# megamon.net
KiCad netlist of a schematic drawn in EAGLE
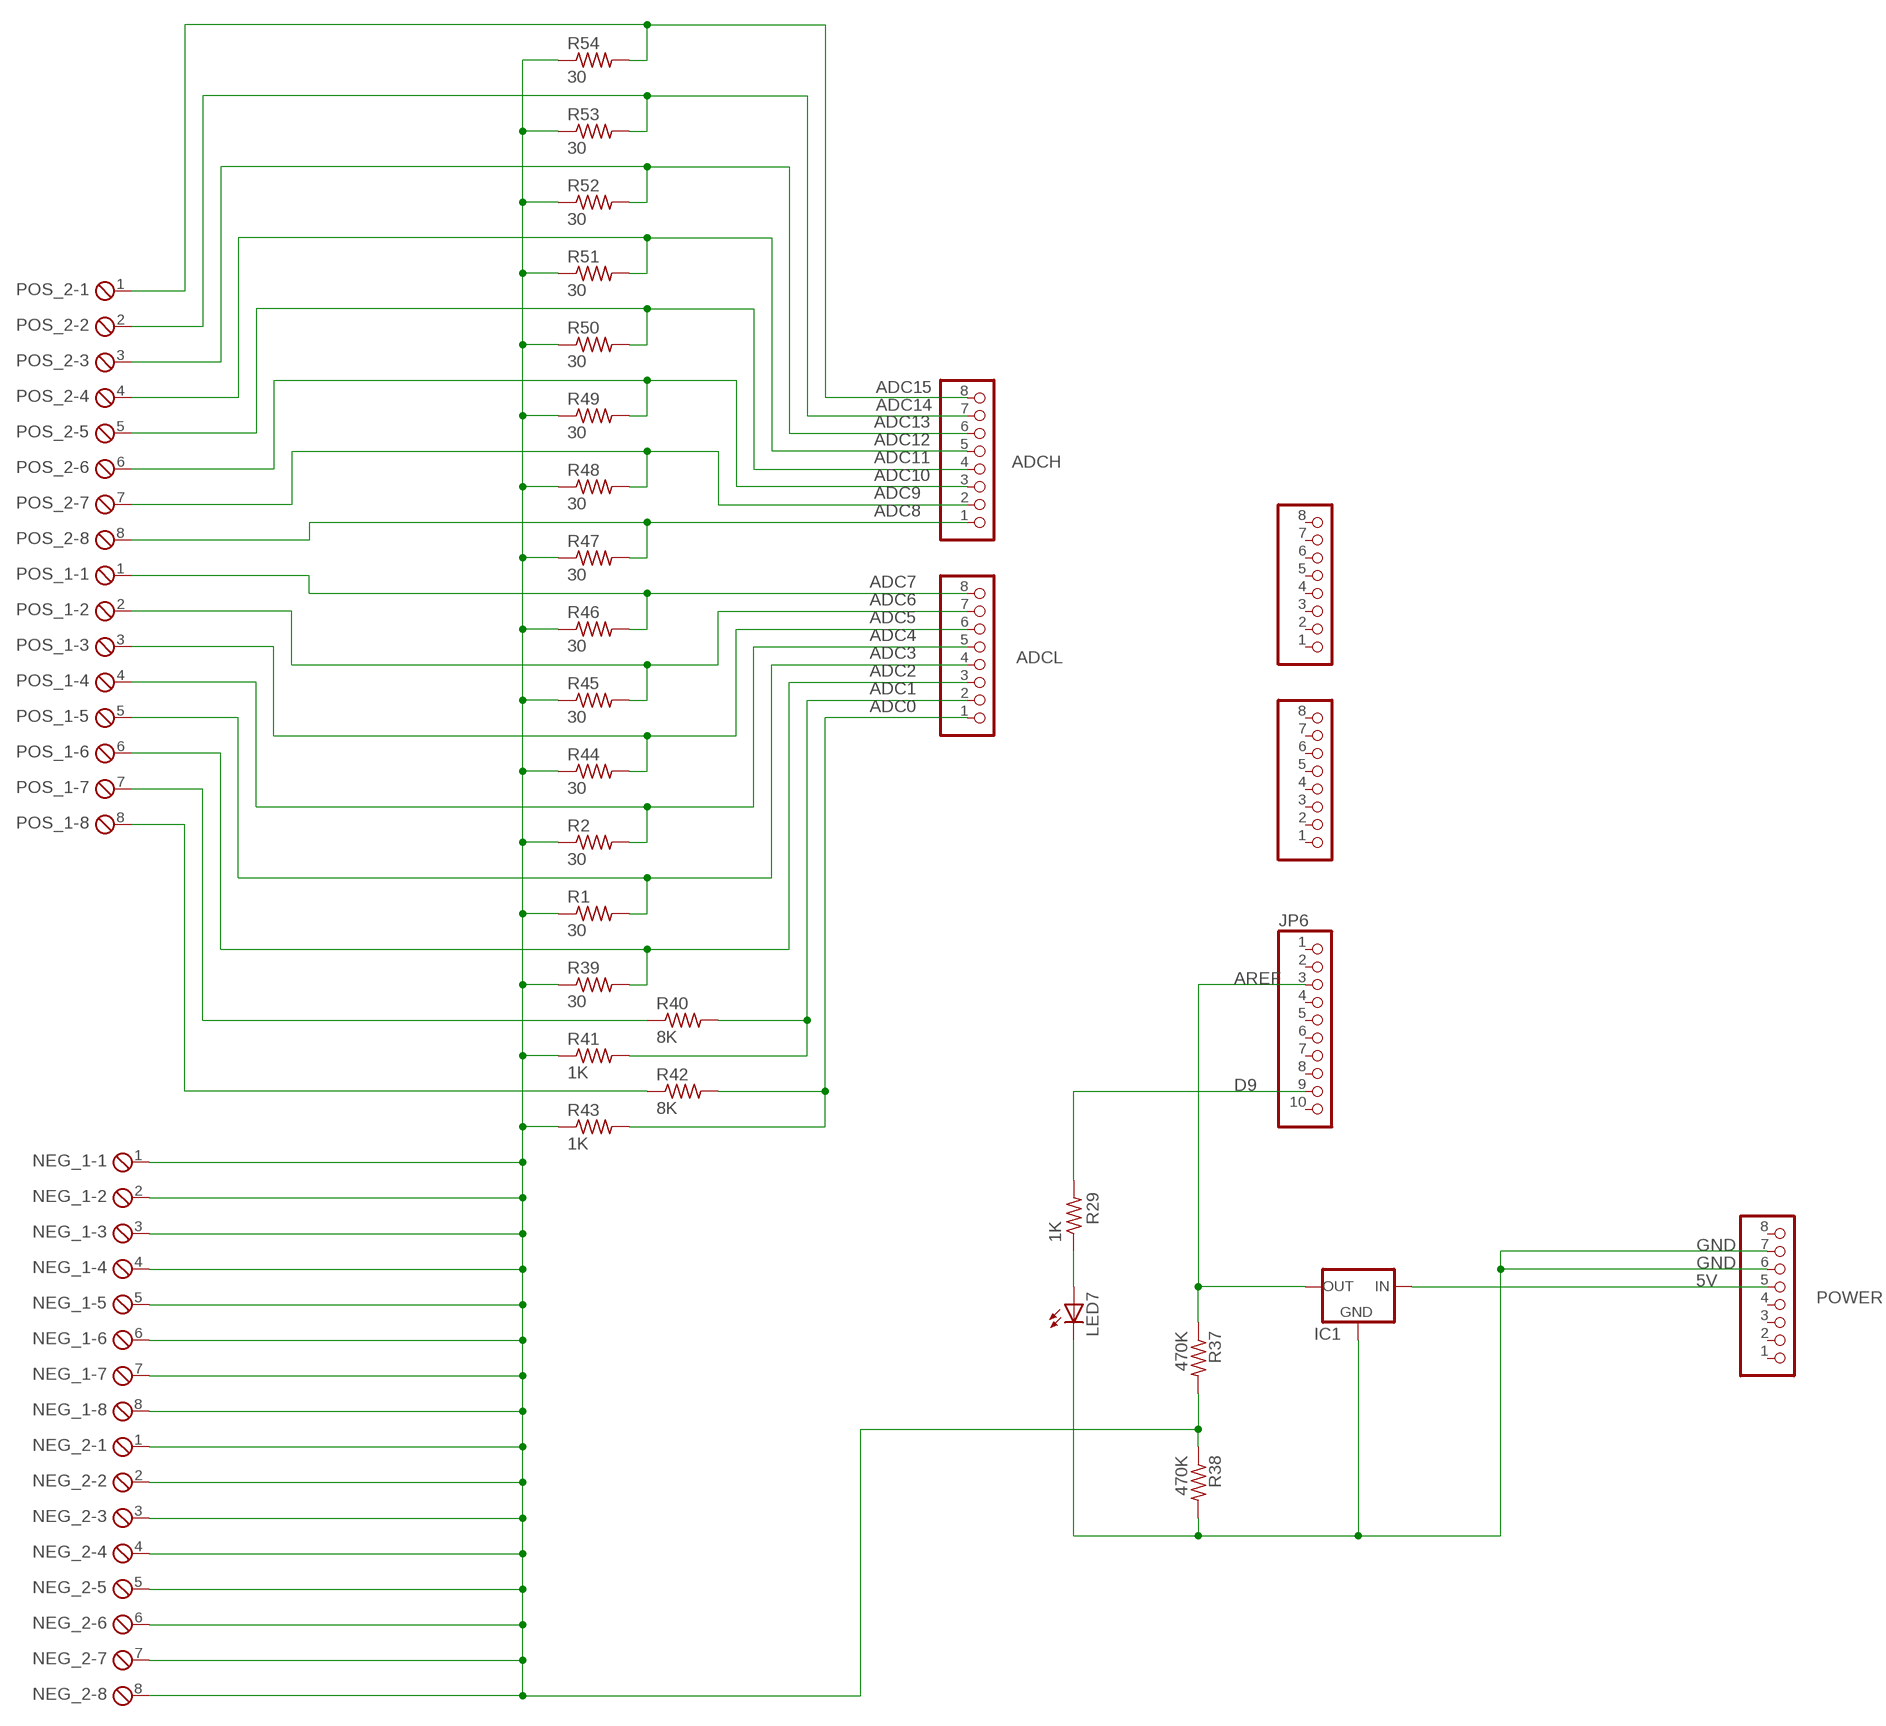
[diagram p0: schematic, sheet 1]

(export (version "E")
  (design (tool "Eeschema 10.0.6"))
  (components
    (comp (ref "ADCH")
      (value "PINHD-1X8")
      (footprint "eagle-import:1X08")
      (libsource (lib "eagle-import") (part "PINHD-1X8"))
    )
    (comp (ref "ADCL")
      (value "PINHD-1X8")
      (footprint "eagle-import:1X08")
      (libsource (lib "eagle-import") (part "PINHD-1X8"))
    )
    (comp (ref "COMMUNICATION")
      (value "FH254-108DF08500V")
      (footprint "eagle-import:1X08")
      (libsource (lib "eagle-import") (part "0058_FH254-108DF08500V"))
    )
    (comp (ref "IC1")
      (value "MCP1700INLINE")
      (footprint "eagle-import:TO92-INLINE")
      (libsource (lib "eagle-import") (part "MCP1700INLINE"))
    )
    (comp (ref "JP6")
      (value "FH254-110DF08500V")
      (footprint "eagle-import:1X10")
      (fields (field (name "PART_NUMBER") "FH254-110DF08500T30"))
      (libsource (lib "eagle-import") (part "1216_FH254-110DF08500T30"))
    )
    (comp (ref "LED7")
      (value "green")
      (footprint "eagle-import:LED3MM")
      (libsource (lib "eagle-import") (part "LED3MM"))
    )
    (comp (ref "NEG_1")
      (value "MPT8")
      (footprint "eagle-import:8POL254")
      (libsource (lib "eagle-import") (part "MPT8"))
    )
    (comp (ref "NEG_2")
      (value "MPT8")
      (footprint "eagle-import:8POL254")
      (libsource (lib "eagle-import") (part "MPT8"))
    )
    (comp (ref "POS_1")
      (value "MPT8")
      (footprint "eagle-import:8POL254")
      (libsource (lib "eagle-import") (part "MPT8"))
    )
    (comp (ref "POS_2")
      (value "MPT8")
      (footprint "eagle-import:8POL254")
      (libsource (lib "eagle-import") (part "MPT8"))
    )
    (comp (ref "POWER")
      (value "PINHD-1X8")
      (footprint "eagle-import:1X08")
      (libsource (lib "eagle-import") (part "PINHD-1X8"))
    )
    (comp (ref "PWML")
      (value "FH254-108DF08500V")
      (footprint "eagle-import:1X08")
      (fields (field (name "PART_NUMBER") "FH254-108DF08500T20"))
      (libsource (lib "eagle-import") (part "1218_FH254-108DF08500T20"))
    )
    (comp (ref "R1")
      (value "30")
      (footprint "eagle-import:0204_7")
      (libsource (lib "eagle-import") (part "R-US_0204/7"))
    )
    (comp (ref "R2")
      (value "30")
      (footprint "eagle-import:0204_7")
      (libsource (lib "eagle-import") (part "R-US_0204/7"))
    )
    (comp (ref "R29")
      (value "1K")
      (footprint "eagle-import:0204_7")
      (libsource (lib "eagle-import") (part "R-US_0204/7"))
    )
    (comp (ref "R37")
      (value "470K")
      (footprint "eagle-import:0204_7")
      (libsource (lib "eagle-import") (part "R-US_0204/7"))
    )
    (comp (ref "R38")
      (value "470K")
      (footprint "eagle-import:0204_7")
      (libsource (lib "eagle-import") (part "R-US_0204/7"))
    )
    (comp (ref "R39")
      (value "30")
      (footprint "eagle-import:0204_7")
      (libsource (lib "eagle-import") (part "R-US_0204/7"))
    )
    (comp (ref "R40")
      (value "8K")
      (footprint "eagle-import:0204_7")
      (libsource (lib "eagle-import") (part "R-US_0204/7"))
    )
    (comp (ref "R41")
      (value "1K")
      (footprint "eagle-import:0204_7")
      (libsource (lib "eagle-import") (part "R-US_0204/7"))
    )
    (comp (ref "R42")
      (value "8K")
      (footprint "eagle-import:0204_7")
      (libsource (lib "eagle-import") (part "R-US_0204/7"))
    )
    (comp (ref "R43")
      (value "1K")
      (footprint "eagle-import:0204_7")
      (libsource (lib "eagle-import") (part "R-US_0204/7"))
    )
    (comp (ref "R44")
      (value "30")
      (footprint "eagle-import:0204_7")
      (libsource (lib "eagle-import") (part "R-US_0204/7"))
    )
    (comp (ref "R45")
      (value "30")
      (footprint "eagle-import:0204_7")
      (libsource (lib "eagle-import") (part "R-US_0204/7"))
    )
    (comp (ref "R46")
      (value "30")
      (footprint "eagle-import:0204_7")
      (libsource (lib "eagle-import") (part "R-US_0204/7"))
    )
    (comp (ref "R47")
      (value "30")
      (footprint "eagle-import:0204_7")
      (libsource (lib "eagle-import") (part "R-US_0204/7"))
    )
    (comp (ref "R48")
      (value "30")
      (footprint "eagle-import:0204_7")
      (libsource (lib "eagle-import") (part "R-US_0204/7"))
    )
    (comp (ref "R49")
      (value "30")
      (footprint "eagle-import:0204_7")
      (libsource (lib "eagle-import") (part "R-US_0204/7"))
    )
    (comp (ref "R50")
      (value "30")
      (footprint "eagle-import:0204_7")
      (libsource (lib "eagle-import") (part "R-US_0204/7"))
    )
    (comp (ref "R51")
      (value "30")
      (footprint "eagle-import:0204_7")
      (libsource (lib "eagle-import") (part "R-US_0204/7"))
    )
    (comp (ref "R52")
      (value "30")
      (footprint "eagle-import:0204_7")
      (libsource (lib "eagle-import") (part "R-US_0204/7"))
    )
    (comp (ref "R53")
      (value "30")
      (footprint "eagle-import:0204_7")
      (libsource (lib "eagle-import") (part "R-US_0204/7"))
    )
    (comp (ref "R54")
      (value "30")
      (footprint "eagle-import:0204_7")
      (libsource (lib "eagle-import") (part "R-US_0204/7"))
    )
  )
  (nets
    (net (code "1") (name "/5V") (class "Default")
      (node (ref "IC1") (pin "2") (pinfunction "IN_2") (pintype "input"))
      (node (ref "POWER") (pin "5") (pinfunction "5_5") (pintype "passive"))
    )
    (net (code "2") (name "/ADC0") (class "Default")
      (node (ref "ADCL") (pin "1") (pinfunction "1_1") (pintype "passive"))
      (node (ref "R42") (pin "2") (pinfunction "2_2") (pintype "passive"))
      (node (ref "R43") (pin "2") (pinfunction "2_2") (pintype "passive"))
    )
    (net (code "3") (name "/ADC1") (class "Default")
      (node (ref "ADCL") (pin "2") (pinfunction "2_2") (pintype "passive"))
      (node (ref "R40") (pin "2") (pinfunction "2_2") (pintype "passive"))
      (node (ref "R41") (pin "2") (pinfunction "2_2") (pintype "passive"))
    )
    (net (code "4") (name "/ADC2") (class "Default")
      (node (ref "ADCL") (pin "3") (pinfunction "3_3") (pintype "passive"))
      (node (ref "POS_1") (pin "6") (pinfunction "1_6") (pintype "passive"))
      (node (ref "R39") (pin "2") (pinfunction "2_2") (pintype "passive"))
    )
    (net (code "5") (name "/ADC3") (class "Default")
      (node (ref "ADCL") (pin "4") (pinfunction "4_4") (pintype "passive"))
      (node (ref "POS_1") (pin "5") (pinfunction "1_5") (pintype "passive"))
      (node (ref "R1") (pin "2") (pinfunction "2_2") (pintype "passive"))
    )
    (net (code "6") (name "/ADC4") (class "Default")
      (node (ref "ADCL") (pin "5") (pinfunction "5_5") (pintype "passive"))
      (node (ref "POS_1") (pin "4") (pinfunction "1_4") (pintype "passive"))
      (node (ref "R2") (pin "2") (pinfunction "2_2") (pintype "passive"))
    )
    (net (code "7") (name "/ADC5") (class "Default")
      (node (ref "ADCL") (pin "6") (pinfunction "6_6") (pintype "passive"))
      (node (ref "POS_1") (pin "3") (pinfunction "1_3") (pintype "passive"))
      (node (ref "R44") (pin "2") (pinfunction "2_2") (pintype "passive"))
    )
    (net (code "8") (name "/ADC6") (class "Default")
      (node (ref "ADCL") (pin "7") (pinfunction "7_7") (pintype "passive"))
      (node (ref "POS_1") (pin "2") (pinfunction "1_2") (pintype "passive"))
      (node (ref "R45") (pin "2") (pinfunction "2_2") (pintype "passive"))
    )
    (net (code "9") (name "/ADC7") (class "Default")
      (node (ref "ADCL") (pin "8") (pinfunction "8_8") (pintype "passive"))
      (node (ref "POS_1") (pin "1") (pinfunction "1_1") (pintype "passive"))
      (node (ref "R46") (pin "2") (pinfunction "2_2") (pintype "passive"))
    )
    (net (code "10") (name "/ADC8") (class "Default")
      (node (ref "ADCH") (pin "1") (pinfunction "1_1") (pintype "passive"))
      (node (ref "POS_2") (pin "8") (pinfunction "1_8") (pintype "passive"))
      (node (ref "R47") (pin "2") (pinfunction "2_2") (pintype "passive"))
    )
    (net (code "11") (name "/ADC9") (class "Default")
      (node (ref "ADCH") (pin "2") (pinfunction "2_2") (pintype "passive"))
      (node (ref "POS_2") (pin "7") (pinfunction "1_7") (pintype "passive"))
      (node (ref "R48") (pin "2") (pinfunction "2_2") (pintype "passive"))
    )
    (net (code "12") (name "/ADC10") (class "Default")
      (node (ref "ADCH") (pin "3") (pinfunction "3_3") (pintype "passive"))
      (node (ref "POS_2") (pin "6") (pinfunction "1_6") (pintype "passive"))
      (node (ref "R49") (pin "2") (pinfunction "2_2") (pintype "passive"))
    )
    (net (code "13") (name "/ADC11") (class "Default")
      (node (ref "ADCH") (pin "4") (pinfunction "4_4") (pintype "passive"))
      (node (ref "POS_2") (pin "5") (pinfunction "1_5") (pintype "passive"))
      (node (ref "R50") (pin "2") (pinfunction "2_2") (pintype "passive"))
    )
    (net (code "14") (name "/ADC12") (class "Default")
      (node (ref "ADCH") (pin "5") (pinfunction "5_5") (pintype "passive"))
      (node (ref "POS_2") (pin "4") (pinfunction "1_4") (pintype "passive"))
      (node (ref "R51") (pin "2") (pinfunction "2_2") (pintype "passive"))
    )
    (net (code "15") (name "/ADC13") (class "Default")
      (node (ref "ADCH") (pin "6") (pinfunction "6_6") (pintype "passive"))
      (node (ref "POS_2") (pin "3") (pinfunction "1_3") (pintype "passive"))
      (node (ref "R52") (pin "2") (pinfunction "2_2") (pintype "passive"))
    )
    (net (code "16") (name "/ADC14") (class "Default")
      (node (ref "ADCH") (pin "7") (pinfunction "7_7") (pintype "passive"))
      (node (ref "POS_2") (pin "2") (pinfunction "1_2") (pintype "passive"))
      (node (ref "R53") (pin "2") (pinfunction "2_2") (pintype "passive"))
    )
    (net (code "17") (name "/ADC15") (class "Default")
      (node (ref "ADCH") (pin "8") (pinfunction "8_8") (pintype "passive"))
      (node (ref "POS_2") (pin "1") (pinfunction "1_1") (pintype "passive"))
      (node (ref "R54") (pin "2") (pinfunction "2_2") (pintype "passive"))
    )
    (net (code "18") (name "/AREF") (class "Default")
      (node (ref "IC1") (pin "3") (pinfunction "OUT_3") (pintype "passive"))
      (node (ref "JP6") (pin "3") (pinfunction "3_3") (pintype "passive"))
      (node (ref "R37") (pin "1") (pinfunction "1_1") (pintype "passive"))
    )
    (net (code "19") (name "/D9") (class "Default")
      (node (ref "JP6") (pin "9") (pinfunction "9_9") (pintype "passive"))
      (node (ref "R29") (pin "2") (pinfunction "2_2") (pintype "passive"))
    )
    (net (code "20") (name "/GND") (class "Default")
      (node (ref "IC1") (pin "1") (pinfunction "GND_1") (pintype "input"))
      (node (ref "LED7") (pin "K") (pinfunction "C_K") (pintype "passive"))
      (node (ref "POWER") (pin "6") (pinfunction "6_6") (pintype "passive"))
      (node (ref "POWER") (pin "7") (pinfunction "7_7") (pintype "passive"))
      (node (ref "R38") (pin "2") (pinfunction "2_2") (pintype "passive"))
    )
    (net (code "21") (name "Net-(LED7-PadA)") (class "Default")
      (node (ref "LED7") (pin "A") (pinfunction "A_A") (pintype "passive"))
      (node (ref "R29") (pin "1") (pinfunction "1_1") (pintype "passive"))
    )
    (net (code "22") (name "Net-(NEG_1B-1)") (class "Default")
      (node (ref "NEG_1") (pin "1") (pinfunction "1_1") (pintype "passive"))
      (node (ref "NEG_1") (pin "2") (pinfunction "1_2") (pintype "passive"))
      (node (ref "NEG_1") (pin "3") (pinfunction "1_3") (pintype "passive"))
      (node (ref "NEG_1") (pin "4") (pinfunction "1_4") (pintype "passive"))
      (node (ref "NEG_1") (pin "5") (pinfunction "1_5") (pintype "passive"))
      (node (ref "NEG_1") (pin "6") (pinfunction "1_6") (pintype "passive"))
      (node (ref "NEG_1") (pin "7") (pinfunction "1_7") (pintype "passive"))
      (node (ref "NEG_1") (pin "8") (pinfunction "1_8") (pintype "passive"))
      (node (ref "NEG_2") (pin "1") (pinfunction "1_1") (pintype "passive"))
      (node (ref "NEG_2") (pin "2") (pinfunction "1_2") (pintype "passive"))
      (node (ref "NEG_2") (pin "3") (pinfunction "1_3") (pintype "passive"))
      (node (ref "NEG_2") (pin "4") (pinfunction "1_4") (pintype "passive"))
      (node (ref "NEG_2") (pin "5") (pinfunction "1_5") (pintype "passive"))
      (node (ref "NEG_2") (pin "6") (pinfunction "1_6") (pintype "passive"))
      (node (ref "NEG_2") (pin "7") (pinfunction "1_7") (pintype "passive"))
      (node (ref "NEG_2") (pin "8") (pinfunction "1_8") (pintype "passive"))
      (node (ref "R1") (pin "1") (pinfunction "1_1") (pintype "passive"))
      (node (ref "R2") (pin "1") (pinfunction "1_1") (pintype "passive"))
      (node (ref "R37") (pin "2") (pinfunction "2_2") (pintype "passive"))
      (node (ref "R38") (pin "1") (pinfunction "1_1") (pintype "passive"))
      (node (ref "R39") (pin "1") (pinfunction "1_1") (pintype "passive"))
      (node (ref "R41") (pin "1") (pinfunction "1_1") (pintype "passive"))
      (node (ref "R43") (pin "1") (pinfunction "1_1") (pintype "passive"))
      (node (ref "R44") (pin "1") (pinfunction "1_1") (pintype "passive"))
      (node (ref "R45") (pin "1") (pinfunction "1_1") (pintype "passive"))
      (node (ref "R46") (pin "1") (pinfunction "1_1") (pintype "passive"))
      (node (ref "R47") (pin "1") (pinfunction "1_1") (pintype "passive"))
      (node (ref "R48") (pin "1") (pinfunction "1_1") (pintype "passive"))
      (node (ref "R49") (pin "1") (pinfunction "1_1") (pintype "passive"))
      (node (ref "R50") (pin "1") (pinfunction "1_1") (pintype "passive"))
      (node (ref "R51") (pin "1") (pinfunction "1_1") (pintype "passive"))
      (node (ref "R52") (pin "1") (pinfunction "1_1") (pintype "passive"))
      (node (ref "R53") (pin "1") (pinfunction "1_1") (pintype "passive"))
      (node (ref "R54") (pin "1") (pinfunction "1_1") (pintype "passive"))
    )
    (net (code "23") (name "Net-(POS_1G-1)") (class "Default")
      (node (ref "POS_1") (pin "7") (pinfunction "1_7") (pintype "passive"))
      (node (ref "R40") (pin "1") (pinfunction "1_1") (pintype "passive"))
    )
    (net (code "24") (name "Net-(POS_1H-1)") (class "Default")
      (node (ref "POS_1") (pin "8") (pinfunction "1_8") (pintype "passive"))
      (node (ref "R42") (pin "1") (pinfunction "1_1") (pintype "passive"))
    )
    (net (code "25") (name "unconnected-(COMMUNICATION-Pad1)") (class "Default")
      (node (ref "COMMUNICATION") (pin "1") (pinfunction "1_1") (pintype "passive"))
    )
    (net (code "26") (name "unconnected-(COMMUNICATION-Pad2)") (class "Default")
      (node (ref "COMMUNICATION") (pin "2") (pinfunction "2_2") (pintype "passive"))
    )
    (net (code "27") (name "unconnected-(COMMUNICATION-Pad3)") (class "Default")
      (node (ref "COMMUNICATION") (pin "3") (pinfunction "3_3") (pintype "passive"))
    )
    (net (code "28") (name "unconnected-(COMMUNICATION-Pad4)") (class "Default")
      (node (ref "COMMUNICATION") (pin "4") (pinfunction "4_4") (pintype "passive"))
    )
    (net (code "29") (name "unconnected-(COMMUNICATION-Pad5)") (class "Default")
      (node (ref "COMMUNICATION") (pin "5") (pinfunction "5_5") (pintype "passive"))
    )
    (net (code "30") (name "unconnected-(COMMUNICATION-Pad6)") (class "Default")
      (node (ref "COMMUNICATION") (pin "6") (pinfunction "6_6") (pintype "passive"))
    )
    (net (code "31") (name "unconnected-(COMMUNICATION-Pad7)") (class "Default")
      (node (ref "COMMUNICATION") (pin "7") (pinfunction "7_7") (pintype "passive"))
    )
    (net (code "32") (name "unconnected-(COMMUNICATION-Pad8)") (class "Default")
      (node (ref "COMMUNICATION") (pin "8") (pinfunction "8_8") (pintype "passive"))
    )
    (net (code "33") (name "unconnected-(JP6-Pad1)") (class "Default")
      (node (ref "JP6") (pin "1") (pinfunction "1_1") (pintype "passive"))
    )
    (net (code "34") (name "unconnected-(JP6-Pad2)") (class "Default")
      (node (ref "JP6") (pin "2") (pinfunction "2_2") (pintype "passive"))
    )
    (net (code "35") (name "unconnected-(JP6-Pad4)") (class "Default")
      (node (ref "JP6") (pin "4") (pinfunction "4_4") (pintype "passive"))
    )
    (net (code "36") (name "unconnected-(JP6-Pad5)") (class "Default")
      (node (ref "JP6") (pin "5") (pinfunction "5_5") (pintype "passive"))
    )
    (net (code "37") (name "unconnected-(JP6-Pad6)") (class "Default")
      (node (ref "JP6") (pin "6") (pinfunction "6_6") (pintype "passive"))
    )
    (net (code "38") (name "unconnected-(JP6-Pad7)") (class "Default")
      (node (ref "JP6") (pin "7") (pinfunction "7_7") (pintype "passive"))
    )
    (net (code "39") (name "unconnected-(JP6-Pad8)") (class "Default")
      (node (ref "JP6") (pin "8") (pinfunction "8_8") (pintype "passive"))
    )
    (net (code "40") (name "unconnected-(JP6-Pad10)") (class "Default")
      (node (ref "JP6") (pin "10") (pinfunction "10_10") (pintype "passive"))
    )
    (net (code "41") (name "unconnected-(POWER-Pad1)") (class "Default")
      (node (ref "POWER") (pin "1") (pinfunction "1_1") (pintype "passive"))
    )
    (net (code "42") (name "unconnected-(POWER-Pad2)") (class "Default")
      (node (ref "POWER") (pin "2") (pinfunction "2_2") (pintype "passive"))
    )
    (net (code "43") (name "unconnected-(POWER-Pad3)") (class "Default")
      (node (ref "POWER") (pin "3") (pinfunction "3_3") (pintype "passive"))
    )
    (net (code "44") (name "unconnected-(POWER-Pad4)") (class "Default")
      (node (ref "POWER") (pin "4") (pinfunction "4_4") (pintype "passive"))
    )
    (net (code "45") (name "unconnected-(POWER-Pad8)") (class "Default")
      (node (ref "POWER") (pin "8") (pinfunction "8_8") (pintype "passive"))
    )
    (net (code "46") (name "unconnected-(PWML-Pad1)") (class "Default")
      (node (ref "PWML") (pin "1") (pinfunction "1_1") (pintype "passive"))
    )
    (net (code "47") (name "unconnected-(PWML-Pad2)") (class "Default")
      (node (ref "PWML") (pin "2") (pinfunction "2_2") (pintype "passive"))
    )
    (net (code "48") (name "unconnected-(PWML-Pad3)") (class "Default")
      (node (ref "PWML") (pin "3") (pinfunction "3_3") (pintype "passive"))
    )
    (net (code "49") (name "unconnected-(PWML-Pad4)") (class "Default")
      (node (ref "PWML") (pin "4") (pinfunction "4_4") (pintype "passive"))
    )
    (net (code "50") (name "unconnected-(PWML-Pad5)") (class "Default")
      (node (ref "PWML") (pin "5") (pinfunction "5_5") (pintype "passive"))
    )
    (net (code "51") (name "unconnected-(PWML-Pad6)") (class "Default")
      (node (ref "PWML") (pin "6") (pinfunction "6_6") (pintype "passive"))
    )
    (net (code "52") (name "unconnected-(PWML-Pad7)") (class "Default")
      (node (ref "PWML") (pin "7") (pinfunction "7_7") (pintype "passive"))
    )
    (net (code "53") (name "unconnected-(PWML-Pad8)") (class "Default")
      (node (ref "PWML") (pin "8") (pinfunction "8_8") (pintype "passive"))
    )
  )
)
